# signal2.net
KiCad netlist of a schematic drawn in Altium Designer
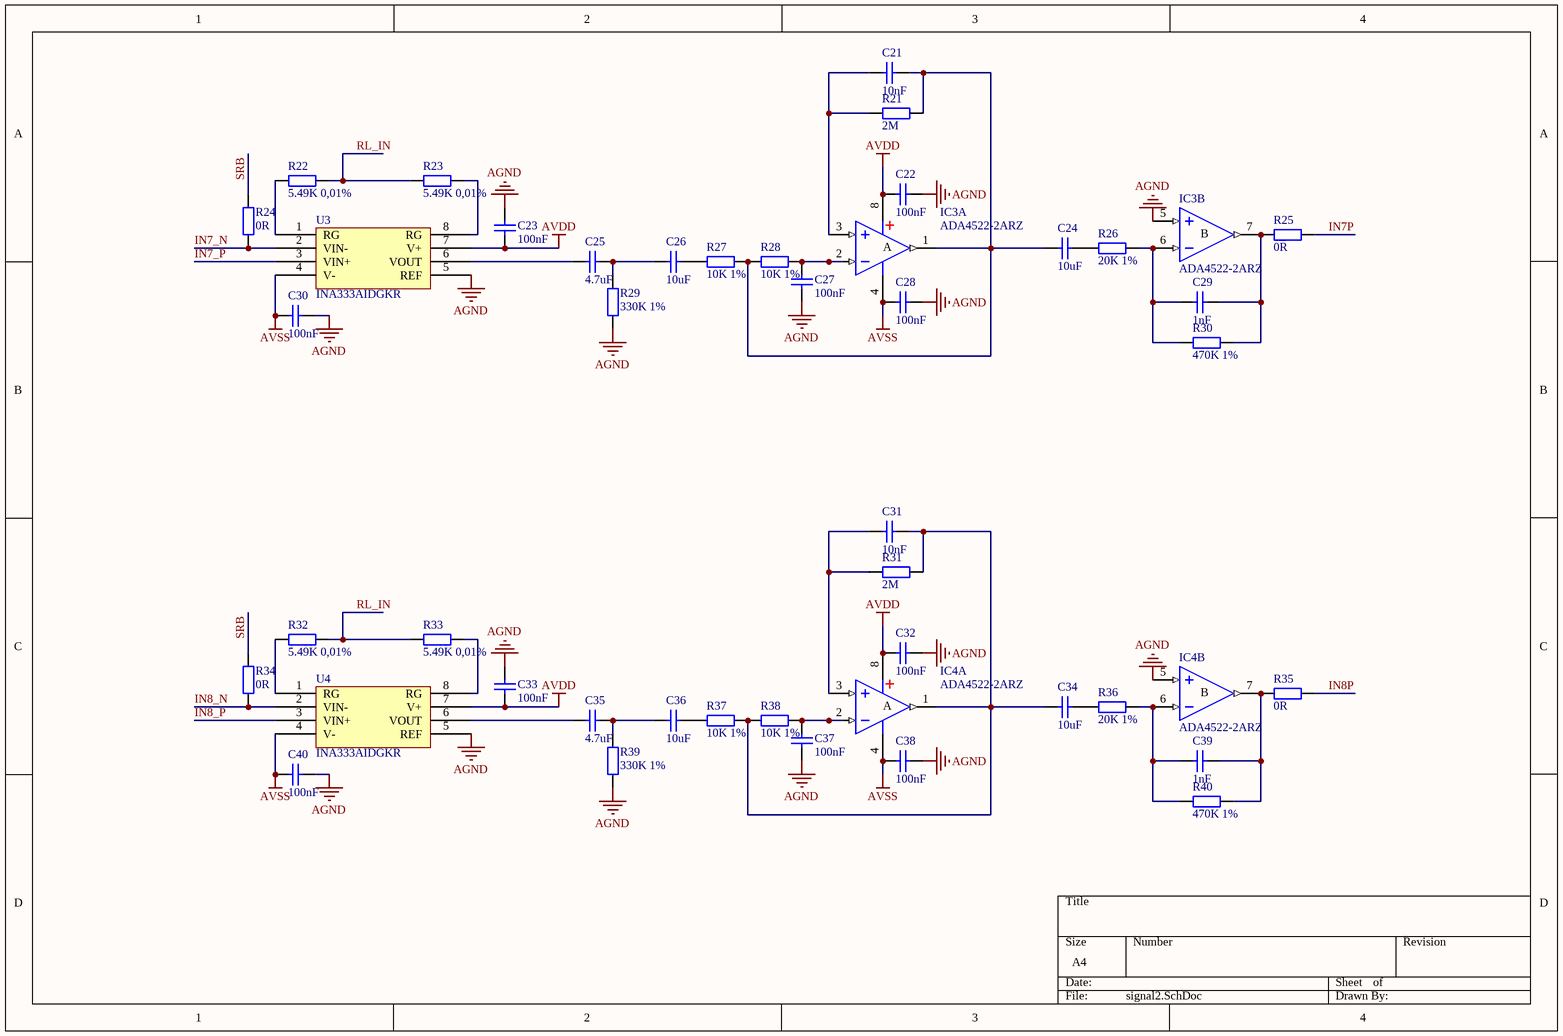
[diagram p0: signal2.SchDoc]

(export (version "E")
  (design (tool "Eeschema 10.0.6"))
  (components
    (comp (ref "C21")
      (value "10nF")
      (footprint "C0603_L")
      (description "贴片电容/MLCC电容")
      (libsource (lib "0.1 - 电阻-电容-电感-保险丝-晶振-晶体-磁珠-电位器-法拉电容-馈通电容") (part "C"))
    )
    (comp (ref "C22")
      (value "100nF")
      (footprint "C0603_L")
      (description "贴片电容/MLCC电容")
      (libsource (lib "0.1 - 电阻-电容-电感-保险丝-晶振-晶体-磁珠-电位器-法拉电容-馈通电容") (part "C"))
    )
    (comp (ref "C23")
      (value "100nF")
      (footprint "C0603_L")
      (description "贴片电容/MLCC电容")
      (libsource (lib "0.1 - 电阻-电容-电感-保险丝-晶振-晶体-磁珠-电位器-法拉电容-馈通电容") (part "C"))
    )
    (comp (ref "C24")
      (value "10uF")
      (footprint "C0603_L")
      (description "贴片电容/MLCC电容")
      (libsource (lib "0.1 - 电阻-电容-电感-保险丝-晶振-晶体-磁珠-电位器-法拉电容-馈通电容") (part "C"))
    )
    (comp (ref "C25")
      (value "4.7uF")
      (footprint "C0603_L")
      (description "贴片电容/MLCC电容")
      (libsource (lib "0.1 - 电阻-电容-电感-保险丝-晶振-晶体-磁珠-电位器-法拉电容-馈通电容") (part "C"))
    )
    (comp (ref "C26")
      (value "10uF")
      (footprint "C0603_L")
      (description "贴片电容/MLCC电容")
      (libsource (lib "0.1 - 电阻-电容-电感-保险丝-晶振-晶体-磁珠-电位器-法拉电容-馈通电容") (part "C"))
    )
    (comp (ref "C27")
      (value "100nF")
      (footprint "C0603_L")
      (description "贴片电容/MLCC电容")
      (libsource (lib "0.1 - 电阻-电容-电感-保险丝-晶振-晶体-磁珠-电位器-法拉电容-馈通电容") (part "C"))
    )
    (comp (ref "C28")
      (value "100nF")
      (footprint "C0603_L")
      (description "贴片电容/MLCC电容")
      (libsource (lib "0.1 - 电阻-电容-电感-保险丝-晶振-晶体-磁珠-电位器-法拉电容-馈通电容") (part "C"))
    )
    (comp (ref "C29")
      (value "1nF")
      (footprint "C0603_L")
      (description "贴片电容/MLCC电容")
      (libsource (lib "0.1 - 电阻-电容-电感-保险丝-晶振-晶体-磁珠-电位器-法拉电容-馈通电容") (part "C"))
    )
    (comp (ref "C30")
      (value "100nF")
      (footprint "C0603_L")
      (description "贴片电容/MLCC电容")
      (libsource (lib "0.1 - 电阻-电容-电感-保险丝-晶振-晶体-磁珠-电位器-法拉电容-馈通电容") (part "C"))
    )
    (comp (ref "C31")
      (value "10nF")
      (footprint "C0603_L")
      (description "贴片电容/MLCC电容")
      (libsource (lib "0.1 - 电阻-电容-电感-保险丝-晶振-晶体-磁珠-电位器-法拉电容-馈通电容") (part "C"))
    )
    (comp (ref "C32")
      (value "100nF")
      (footprint "C0603_L")
      (description "贴片电容/MLCC电容")
      (libsource (lib "0.1 - 电阻-电容-电感-保险丝-晶振-晶体-磁珠-电位器-法拉电容-馈通电容") (part "C"))
    )
    (comp (ref "C33")
      (value "100nF")
      (footprint "C0603_L")
      (description "贴片电容/MLCC电容")
      (libsource (lib "0.1 - 电阻-电容-电感-保险丝-晶振-晶体-磁珠-电位器-法拉电容-馈通电容") (part "C"))
    )
    (comp (ref "C34")
      (value "10uF")
      (footprint "C0603_L")
      (description "贴片电容/MLCC电容")
      (libsource (lib "0.1 - 电阻-电容-电感-保险丝-晶振-晶体-磁珠-电位器-法拉电容-馈通电容") (part "C"))
    )
    (comp (ref "C35")
      (value "4.7uF")
      (footprint "C0603_L")
      (description "贴片电容/MLCC电容")
      (libsource (lib "0.1 - 电阻-电容-电感-保险丝-晶振-晶体-磁珠-电位器-法拉电容-馈通电容") (part "C"))
    )
    (comp (ref "C36")
      (value "10uF")
      (footprint "C0603_L")
      (description "贴片电容/MLCC电容")
      (libsource (lib "0.1 - 电阻-电容-电感-保险丝-晶振-晶体-磁珠-电位器-法拉电容-馈通电容") (part "C"))
    )
    (comp (ref "C37")
      (value "100nF")
      (footprint "C0603_L")
      (description "贴片电容/MLCC电容")
      (libsource (lib "0.1 - 电阻-电容-电感-保险丝-晶振-晶体-磁珠-电位器-法拉电容-馈通电容") (part "C"))
    )
    (comp (ref "C38")
      (value "100nF")
      (footprint "C0603_L")
      (description "贴片电容/MLCC电容")
      (libsource (lib "0.1 - 电阻-电容-电感-保险丝-晶振-晶体-磁珠-电位器-法拉电容-馈通电容") (part "C"))
    )
    (comp (ref "C39")
      (value "1nF")
      (footprint "C0603_L")
      (description "贴片电容/MLCC电容")
      (libsource (lib "0.1 - 电阻-电容-电感-保险丝-晶振-晶体-磁珠-电位器-法拉电容-馈通电容") (part "C"))
    )
    (comp (ref "C40")
      (value "100nF")
      (footprint "C0603_L")
      (description "贴片电容/MLCC电容")
      (libsource (lib "0.1 - 电阻-电容-电感-保险丝-晶振-晶体-磁珠-电位器-法拉电容-馈通电容") (part "C"))
    )
    (comp (ref "IC3")
      (value "ADA4522-2ARZ")
      (footprint "SOIC-8")
      (description "双通道55V、EMI增强型、零漂移、超低噪声、RRO运算放大器")
      (libsource (lib "HT") (part "ADA4522-2ARZ"))
    )
    (comp (ref "IC4")
      (value "ADA4522-2ARZ")
      (footprint "SOIC-8")
      (description "双通道55V、EMI增强型、零漂移、超低噪声、RRO运算放大器")
      (libsource (lib "HT") (part "ADA4522-2ARZ"))
    )
    (comp (ref "R21")
      (value "2M")
      (footprint "R0603_L")
      (description "贴片电阻")
      (libsource (lib "0.1 - 电阻-电容-电感-保险丝-晶振-晶体-磁珠-电位器-法拉电容-馈通电容") (part "R"))
    )
    (comp (ref "R22")
      (value "5.49K 0,01%")
      (footprint "R0603_M")
      (description "贴片电阻")
      (libsource (lib "0.1 - 电阻-电容-电感-保险丝-晶振-晶体-磁珠-电位器-法拉电容-馈通电容") (part "R"))
    )
    (comp (ref "R23")
      (value "5.49K 0,01%")
      (footprint "R0603_M")
      (description "贴片电阻")
      (libsource (lib "0.1 - 电阻-电容-电感-保险丝-晶振-晶体-磁珠-电位器-法拉电容-馈通电容") (part "R"))
    )
    (comp (ref "R24")
      (value "0R")
      (footprint "R0603_L")
      (description "贴片电阻")
      (libsource (lib "0.1 - 电阻-电容-电感-保险丝-晶振-晶体-磁珠-电位器-法拉电容-馈通电容") (part "R"))
    )
    (comp (ref "R25")
      (value "0R")
      (footprint "R0603_L")
      (description "贴片电阻")
      (libsource (lib "0.1 - 电阻-电容-电感-保险丝-晶振-晶体-磁珠-电位器-法拉电容-馈通电容") (part "R"))
    )
    (comp (ref "R26")
      (value "20K 1%")
      (footprint "R0603_L")
      (description "贴片电阻")
      (libsource (lib "0.1 - 电阻-电容-电感-保险丝-晶振-晶体-磁珠-电位器-法拉电容-馈通电容") (part "R"))
    )
    (comp (ref "R27")
      (value "10K 1%")
      (footprint "R0603_L")
      (description "贴片电阻")
      (libsource (lib "0.1 - 电阻-电容-电感-保险丝-晶振-晶体-磁珠-电位器-法拉电容-馈通电容") (part "R"))
    )
    (comp (ref "R28")
      (value "10K 1%")
      (footprint "R0603_L")
      (description "贴片电阻")
      (libsource (lib "0.1 - 电阻-电容-电感-保险丝-晶振-晶体-磁珠-电位器-法拉电容-馈通电容") (part "R"))
    )
    (comp (ref "R29")
      (value "330K 1%")
      (footprint "R0603_L")
      (description "贴片电阻")
      (libsource (lib "0.1 - 电阻-电容-电感-保险丝-晶振-晶体-磁珠-电位器-法拉电容-馈通电容") (part "R"))
    )
    (comp (ref "R30")
      (value "470K 1%")
      (footprint "R0603_L")
      (description "贴片电阻")
      (libsource (lib "0.1 - 电阻-电容-电感-保险丝-晶振-晶体-磁珠-电位器-法拉电容-馈通电容") (part "R"))
    )
    (comp (ref "R31")
      (value "2M")
      (footprint "R0603_L")
      (description "贴片电阻")
      (libsource (lib "0.1 - 电阻-电容-电感-保险丝-晶振-晶体-磁珠-电位器-法拉电容-馈通电容") (part "R"))
    )
    (comp (ref "R32")
      (value "5.49K 0,01%")
      (footprint "R0603_M")
      (description "贴片电阻")
      (libsource (lib "0.1 - 电阻-电容-电感-保险丝-晶振-晶体-磁珠-电位器-法拉电容-馈通电容") (part "R"))
    )
    (comp (ref "R33")
      (value "5.49K 0,01%")
      (footprint "R0603_M")
      (description "贴片电阻")
      (libsource (lib "0.1 - 电阻-电容-电感-保险丝-晶振-晶体-磁珠-电位器-法拉电容-馈通电容") (part "R"))
    )
    (comp (ref "R34")
      (value "0R")
      (footprint "R0603_L")
      (description "贴片电阻")
      (libsource (lib "0.1 - 电阻-电容-电感-保险丝-晶振-晶体-磁珠-电位器-法拉电容-馈通电容") (part "R"))
    )
    (comp (ref "R35")
      (value "0R")
      (footprint "R0603_L")
      (description "贴片电阻")
      (libsource (lib "0.1 - 电阻-电容-电感-保险丝-晶振-晶体-磁珠-电位器-法拉电容-馈通电容") (part "R"))
    )
    (comp (ref "R36")
      (value "20K 1%")
      (footprint "R0603_L")
      (description "贴片电阻")
      (libsource (lib "0.1 - 电阻-电容-电感-保险丝-晶振-晶体-磁珠-电位器-法拉电容-馈通电容") (part "R"))
    )
    (comp (ref "R37")
      (value "10K 1%")
      (footprint "R0603_L")
      (description "贴片电阻")
      (libsource (lib "0.1 - 电阻-电容-电感-保险丝-晶振-晶体-磁珠-电位器-法拉电容-馈通电容") (part "R"))
    )
    (comp (ref "R38")
      (value "10K 1%")
      (footprint "R0603_L")
      (description "贴片电阻")
      (libsource (lib "0.1 - 电阻-电容-电感-保险丝-晶振-晶体-磁珠-电位器-法拉电容-馈通电容") (part "R"))
    )
    (comp (ref "R39")
      (value "330K 1%")
      (footprint "R0603_L")
      (description "贴片电阻")
      (libsource (lib "0.1 - 电阻-电容-电感-保险丝-晶振-晶体-磁珠-电位器-法拉电容-馈通电容") (part "R"))
    )
    (comp (ref "R40")
      (value "470K 1%")
      (footprint "R0603_L")
      (description "贴片电阻")
      (libsource (lib "0.1 - 电阻-电容-电感-保险丝-晶振-晶体-磁珠-电位器-法拉电容-馈通电容") (part "R"))
    )
    (comp (ref "U3")
      (value "INA333AIDGKR")
      (footprint "MSOP8_N")
      (description "INA333 低功耗、零漂移、精密仪表放大器")
      (libsource (lib "HT") (part "INA333AIDGKR"))
    )
    (comp (ref "U4")
      (value "INA333AIDGKR")
      (footprint "MSOP8_N")
      (description "INA333 低功耗、零漂移、精密仪表放大器")
      (libsource (lib "HT") (part "INA333AIDGKR"))
    )
  )
  (nets
    (net (code "1") (name "/IN7P") (class "Default")
      (node (ref "R25") (pin "1") (pinfunction "1_1") (pintype "passive"))
    )
    (net (code "2") (name "/IN7_N") (class "Default")
      (node (ref "R24") (pin "2") (pinfunction "2_2") (pintype "passive"))
      (node (ref "U3") (pin "2") (pinfunction "VIN-_2") (pintype "passive"))
    )
    (net (code "3") (name "/IN7_P") (class "Default")
      (node (ref "U3") (pin "3") (pinfunction "VIN+_3") (pintype "passive"))
    )
    (net (code "4") (name "/IN8P") (class "Default")
      (node (ref "R35") (pin "1") (pinfunction "1_1") (pintype "passive"))
    )
    (net (code "5") (name "/IN8_N") (class "Default")
      (node (ref "R34") (pin "2") (pinfunction "2_2") (pintype "passive"))
      (node (ref "U4") (pin "2") (pinfunction "VIN-_2") (pintype "passive"))
    )
    (net (code "6") (name "/IN8_P") (class "Default")
      (node (ref "U4") (pin "3") (pinfunction "VIN+_3") (pintype "passive"))
    )
    (net (code "7") (name "/RL_IN") (class "Default")
      (node (ref "R22") (pin "2") (pinfunction "2_2") (pintype "passive"))
      (node (ref "R23") (pin "1") (pinfunction "1_1") (pintype "passive"))
      (node (ref "R32") (pin "2") (pinfunction "2_2") (pintype "passive"))
      (node (ref "R33") (pin "1") (pinfunction "1_1") (pintype "passive"))
    )
    (net (code "8") (name "/SRB") (class "Default")
      (node (ref "R24") (pin "1") (pinfunction "1_1") (pintype "passive"))
      (node (ref "R34") (pin "1") (pinfunction "1_1") (pintype "passive"))
    )
    (net (code "9") (name "AGND") (class "Default")
      (node (ref "C22") (pin "2") (pinfunction "2_2") (pintype "passive"))
      (node (ref "C23") (pin "1") (pinfunction "1_1") (pintype "passive"))
      (node (ref "C27") (pin "1") (pinfunction "1_1") (pintype "passive"))
      (node (ref "C28") (pin "2") (pinfunction "2_2") (pintype "passive"))
      (node (ref "C30") (pin "1") (pinfunction "1_1") (pintype "passive"))
      (node (ref "C32") (pin "2") (pinfunction "2_2") (pintype "passive"))
      (node (ref "C33") (pin "1") (pinfunction "1_1") (pintype "passive"))
      (node (ref "C37") (pin "1") (pinfunction "1_1") (pintype "passive"))
      (node (ref "C38") (pin "2") (pinfunction "2_2") (pintype "passive"))
      (node (ref "C40") (pin "1") (pinfunction "1_1") (pintype "passive"))
      (node (ref "IC3") (pin "5") (pinfunction "IN+_5") (pintype "input"))
      (node (ref "IC4") (pin "5") (pinfunction "IN+_5") (pintype "input"))
      (node (ref "R29") (pin "1") (pinfunction "1_1") (pintype "passive"))
      (node (ref "R39") (pin "1") (pinfunction "1_1") (pintype "passive"))
      (node (ref "U3") (pin "5") (pinfunction "REF_5") (pintype "passive"))
      (node (ref "U4") (pin "5") (pinfunction "REF_5") (pintype "passive"))
    )
    (net (code "10") (name "AVDD") (class "Default")
      (node (ref "C22") (pin "1") (pinfunction "1_1") (pintype "passive"))
      (node (ref "C23") (pin "2") (pinfunction "2_2") (pintype "passive"))
      (node (ref "C32") (pin "1") (pinfunction "1_1") (pintype "passive"))
      (node (ref "C33") (pin "2") (pinfunction "2_2") (pintype "passive"))
      (node (ref "IC3") (pin "8") (pinfunction "V+_8") (pintype "power_in"))
      (node (ref "IC4") (pin "8") (pinfunction "V+_8") (pintype "power_in"))
      (node (ref "U3") (pin "7") (pinfunction "V+_7") (pintype "passive"))
      (node (ref "U4") (pin "7") (pinfunction "V+_7") (pintype "passive"))
    )
    (net (code "11") (name "AVSS") (class "Default")
      (node (ref "C28") (pin "1") (pinfunction "1_1") (pintype "passive"))
      (node (ref "C30") (pin "2") (pinfunction "2_2") (pintype "passive"))
      (node (ref "C38") (pin "1") (pinfunction "1_1") (pintype "passive"))
      (node (ref "C40") (pin "2") (pinfunction "2_2") (pintype "passive"))
      (node (ref "IC3") (pin "4") (pinfunction "V-_4") (pintype "power_in"))
      (node (ref "IC4") (pin "4") (pinfunction "V-_4") (pintype "power_in"))
      (node (ref "U3") (pin "4") (pinfunction "V-_4") (pintype "passive"))
      (node (ref "U4") (pin "4") (pinfunction "V-_4") (pintype "passive"))
    )
    (net (code "12") (name "Net-(C24-Pad2)") (class "Default")
      (node (ref "C24") (pin "2") (pinfunction "2_2") (pintype "passive"))
      (node (ref "R26") (pin "2") (pinfunction "2_2") (pintype "passive"))
    )
    (net (code "13") (name "Net-(C25-Pad2)") (class "Default")
      (node (ref "C25") (pin "2") (pinfunction "2_2") (pintype "passive"))
      (node (ref "C26") (pin "1") (pinfunction "1_1") (pintype "passive"))
      (node (ref "R29") (pin "2") (pinfunction "2_2") (pintype "passive"))
    )
    (net (code "14") (name "Net-(C26-Pad2)") (class "Default")
      (node (ref "C26") (pin "2") (pinfunction "2_2") (pintype "passive"))
      (node (ref "R27") (pin "2") (pinfunction "2_2") (pintype "passive"))
    )
    (net (code "15") (name "Net-(C34-Pad2)") (class "Default")
      (node (ref "C34") (pin "2") (pinfunction "2_2") (pintype "passive"))
      (node (ref "R36") (pin "2") (pinfunction "2_2") (pintype "passive"))
    )
    (net (code "16") (name "Net-(C35-Pad2)") (class "Default")
      (node (ref "C35") (pin "2") (pinfunction "2_2") (pintype "passive"))
      (node (ref "C36") (pin "1") (pinfunction "1_1") (pintype "passive"))
      (node (ref "R39") (pin "2") (pinfunction "2_2") (pintype "passive"))
    )
    (net (code "17") (name "Net-(C36-Pad2)") (class "Default")
      (node (ref "C36") (pin "2") (pinfunction "2_2") (pintype "passive"))
      (node (ref "R37") (pin "2") (pinfunction "2_2") (pintype "passive"))
    )
    (net (code "18") (name "Net-(IC3A-IN+)") (class "Default")
      (node (ref "C21") (pin "1") (pinfunction "1_1") (pintype "passive"))
      (node (ref "IC3") (pin "3") (pinfunction "IN+_3") (pintype "input"))
      (node (ref "R21") (pin "2") (pinfunction "2_2") (pintype "passive"))
    )
    (net (code "19") (name "Net-(IC3A-IN-)") (class "Default")
      (node (ref "C27") (pin "2") (pinfunction "2_2") (pintype "passive"))
      (node (ref "IC3") (pin "2") (pinfunction "IN-_2") (pintype "input"))
      (node (ref "R28") (pin "1") (pinfunction "1_1") (pintype "passive"))
    )
    (net (code "20") (name "Net-(IC3A-OUT)") (class "Default")
      (node (ref "C21") (pin "2") (pinfunction "2_2") (pintype "passive"))
      (node (ref "C24") (pin "1") (pinfunction "1_1") (pintype "passive"))
      (node (ref "IC3") (pin "1") (pinfunction "OUT_1") (pintype "output"))
      (node (ref "R21") (pin "1") (pinfunction "1_1") (pintype "passive"))
      (node (ref "R27") (pin "1") (pinfunction "1_1") (pintype "passive"))
      (node (ref "R28") (pin "2") (pinfunction "2_2") (pintype "passive"))
    )
    (net (code "21") (name "Net-(IC3B-IN-)") (class "Default")
      (node (ref "C29") (pin "1") (pinfunction "1_1") (pintype "passive"))
      (node (ref "IC3") (pin "6") (pinfunction "IN-_6") (pintype "input"))
      (node (ref "R26") (pin "1") (pinfunction "1_1") (pintype "passive"))
      (node (ref "R30") (pin "2") (pinfunction "2_2") (pintype "passive"))
    )
    (net (code "22") (name "Net-(IC3B-OUT)") (class "Default")
      (node (ref "C29") (pin "2") (pinfunction "2_2") (pintype "passive"))
      (node (ref "IC3") (pin "7") (pinfunction "OUT_7") (pintype "output"))
      (node (ref "R25") (pin "2") (pinfunction "2_2") (pintype "passive"))
      (node (ref "R30") (pin "1") (pinfunction "1_1") (pintype "passive"))
    )
    (net (code "23") (name "Net-(IC4A-IN+)") (class "Default")
      (node (ref "C31") (pin "1") (pinfunction "1_1") (pintype "passive"))
      (node (ref "IC4") (pin "3") (pinfunction "IN+_3") (pintype "input"))
      (node (ref "R31") (pin "2") (pinfunction "2_2") (pintype "passive"))
    )
    (net (code "24") (name "Net-(IC4A-IN-)") (class "Default")
      (node (ref "C37") (pin "2") (pinfunction "2_2") (pintype "passive"))
      (node (ref "IC4") (pin "2") (pinfunction "IN-_2") (pintype "input"))
      (node (ref "R38") (pin "1") (pinfunction "1_1") (pintype "passive"))
    )
    (net (code "25") (name "Net-(IC4A-OUT)") (class "Default")
      (node (ref "C31") (pin "2") (pinfunction "2_2") (pintype "passive"))
      (node (ref "C34") (pin "1") (pinfunction "1_1") (pintype "passive"))
      (node (ref "IC4") (pin "1") (pinfunction "OUT_1") (pintype "output"))
      (node (ref "R31") (pin "1") (pinfunction "1_1") (pintype "passive"))
      (node (ref "R37") (pin "1") (pinfunction "1_1") (pintype "passive"))
      (node (ref "R38") (pin "2") (pinfunction "2_2") (pintype "passive"))
    )
    (net (code "26") (name "Net-(IC4B-IN-)") (class "Default")
      (node (ref "C39") (pin "1") (pinfunction "1_1") (pintype "passive"))
      (node (ref "IC4") (pin "6") (pinfunction "IN-_6") (pintype "input"))
      (node (ref "R36") (pin "1") (pinfunction "1_1") (pintype "passive"))
      (node (ref "R40") (pin "2") (pinfunction "2_2") (pintype "passive"))
    )
    (net (code "27") (name "Net-(IC4B-OUT)") (class "Default")
      (node (ref "C39") (pin "2") (pinfunction "2_2") (pintype "passive"))
      (node (ref "IC4") (pin "7") (pinfunction "OUT_7") (pintype "output"))
      (node (ref "R35") (pin "2") (pinfunction "2_2") (pintype "passive"))
      (node (ref "R40") (pin "1") (pinfunction "1_1") (pintype "passive"))
    )
    (net (code "28") (name "Net-(R22-Pad1)") (class "Default")
      (node (ref "R22") (pin "1") (pinfunction "1_1") (pintype "passive"))
      (node (ref "U3") (pin "1") (pinfunction "RG_1") (pintype "passive"))
    )
    (net (code "29") (name "Net-(R23-Pad2)") (class "Default")
      (node (ref "R23") (pin "2") (pinfunction "2_2") (pintype "passive"))
      (node (ref "U3") (pin "8") (pinfunction "RG_8") (pintype "passive"))
    )
    (net (code "30") (name "Net-(R32-Pad1)") (class "Default")
      (node (ref "R32") (pin "1") (pinfunction "1_1") (pintype "passive"))
      (node (ref "U4") (pin "1") (pinfunction "RG_1") (pintype "passive"))
    )
    (net (code "31") (name "Net-(R33-Pad2)") (class "Default")
      (node (ref "R33") (pin "2") (pinfunction "2_2") (pintype "passive"))
      (node (ref "U4") (pin "8") (pinfunction "RG_8") (pintype "passive"))
    )
    (net (code "32") (name "Net-(U3-VOUT)") (class "Default")
      (node (ref "C25") (pin "1") (pinfunction "1_1") (pintype "passive"))
      (node (ref "U3") (pin "6") (pinfunction "VOUT_6") (pintype "passive"))
    )
    (net (code "33") (name "Net-(U4-VOUT)") (class "Default")
      (node (ref "C35") (pin "1") (pinfunction "1_1") (pintype "passive"))
      (node (ref "U4") (pin "6") (pinfunction "VOUT_6") (pintype "passive"))
    )
  )
)
